# Precharge_2019_Test.net
KiCad netlist of a schematic drawn in EAGLE
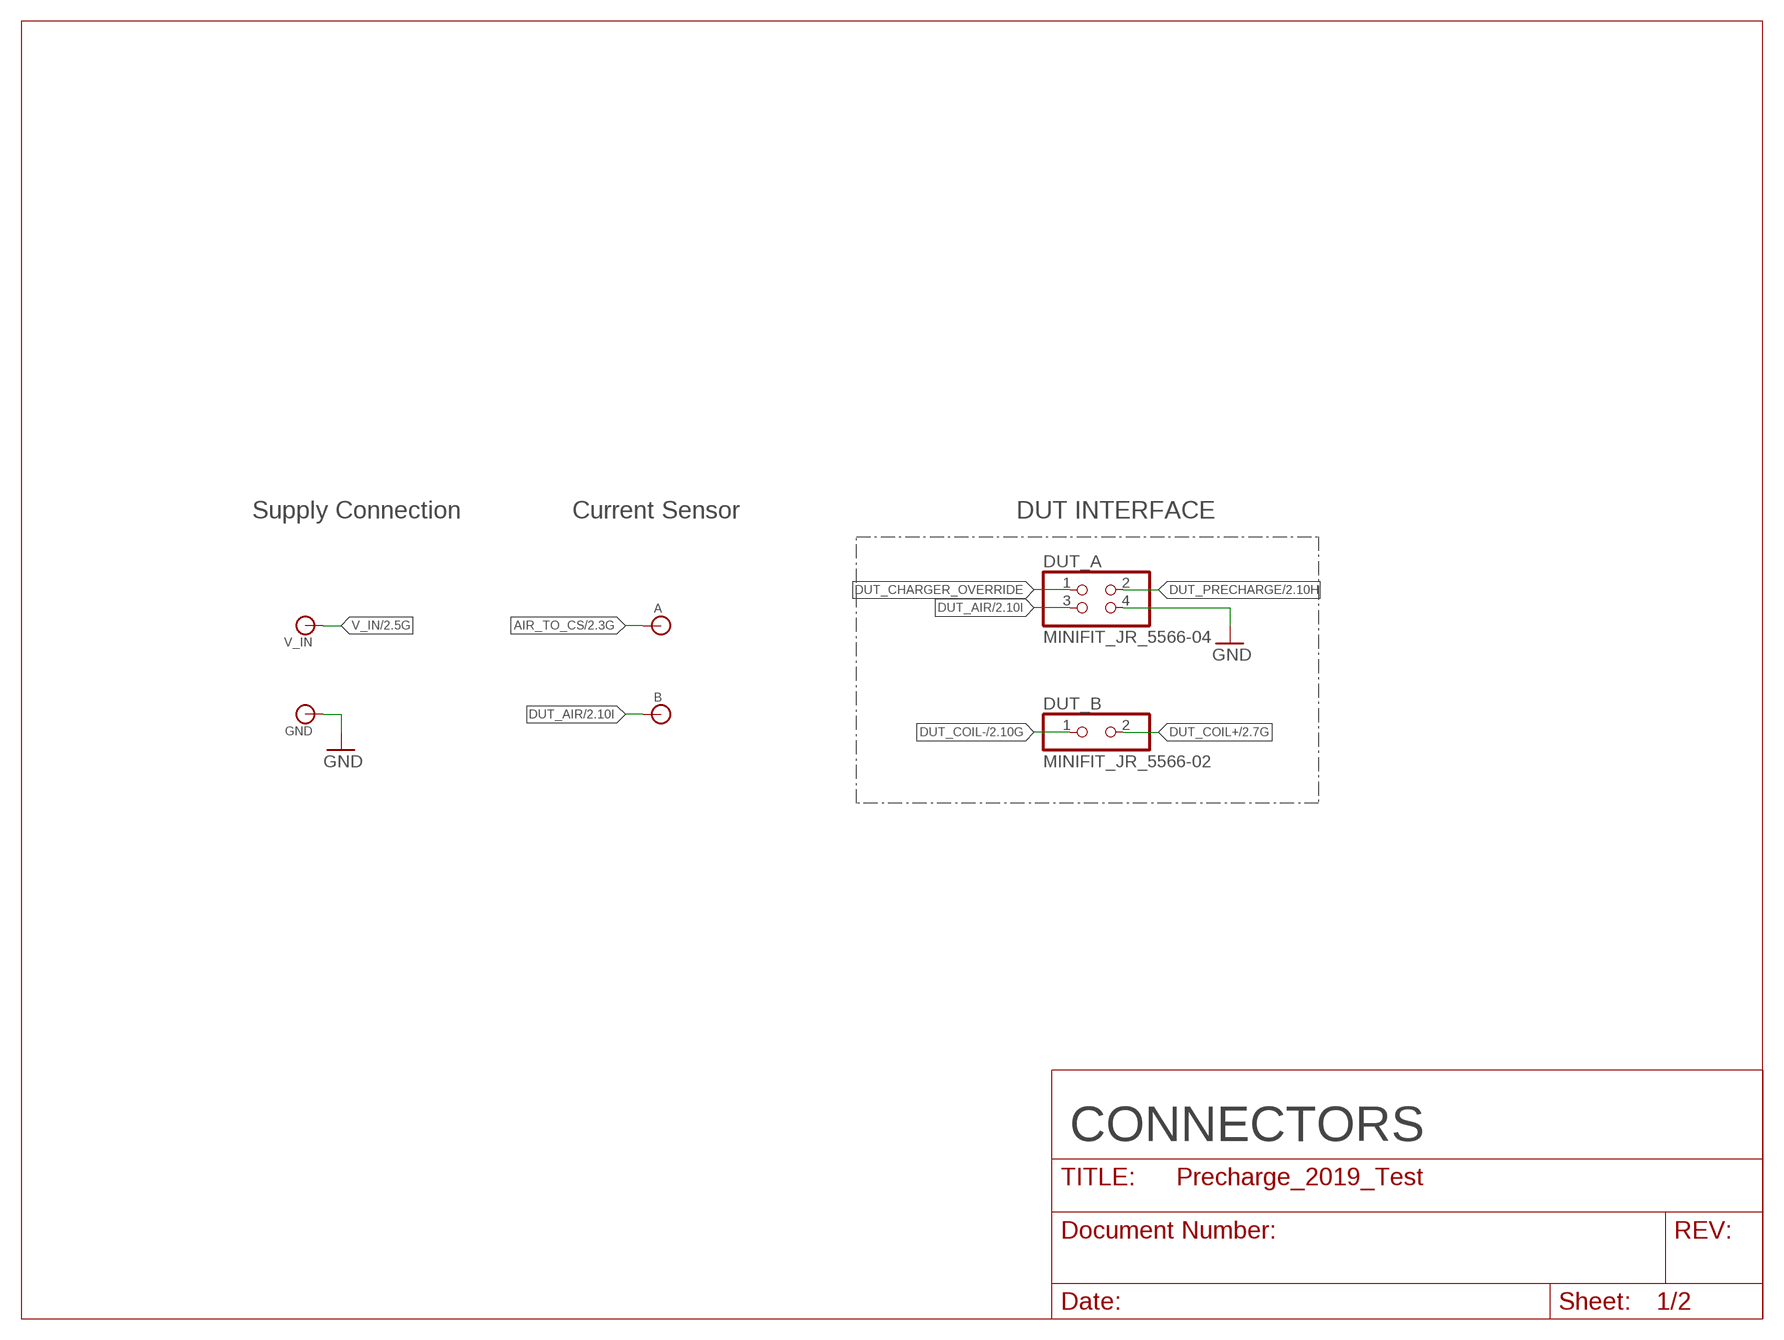
[diagram p0: schematic, sheet 1]
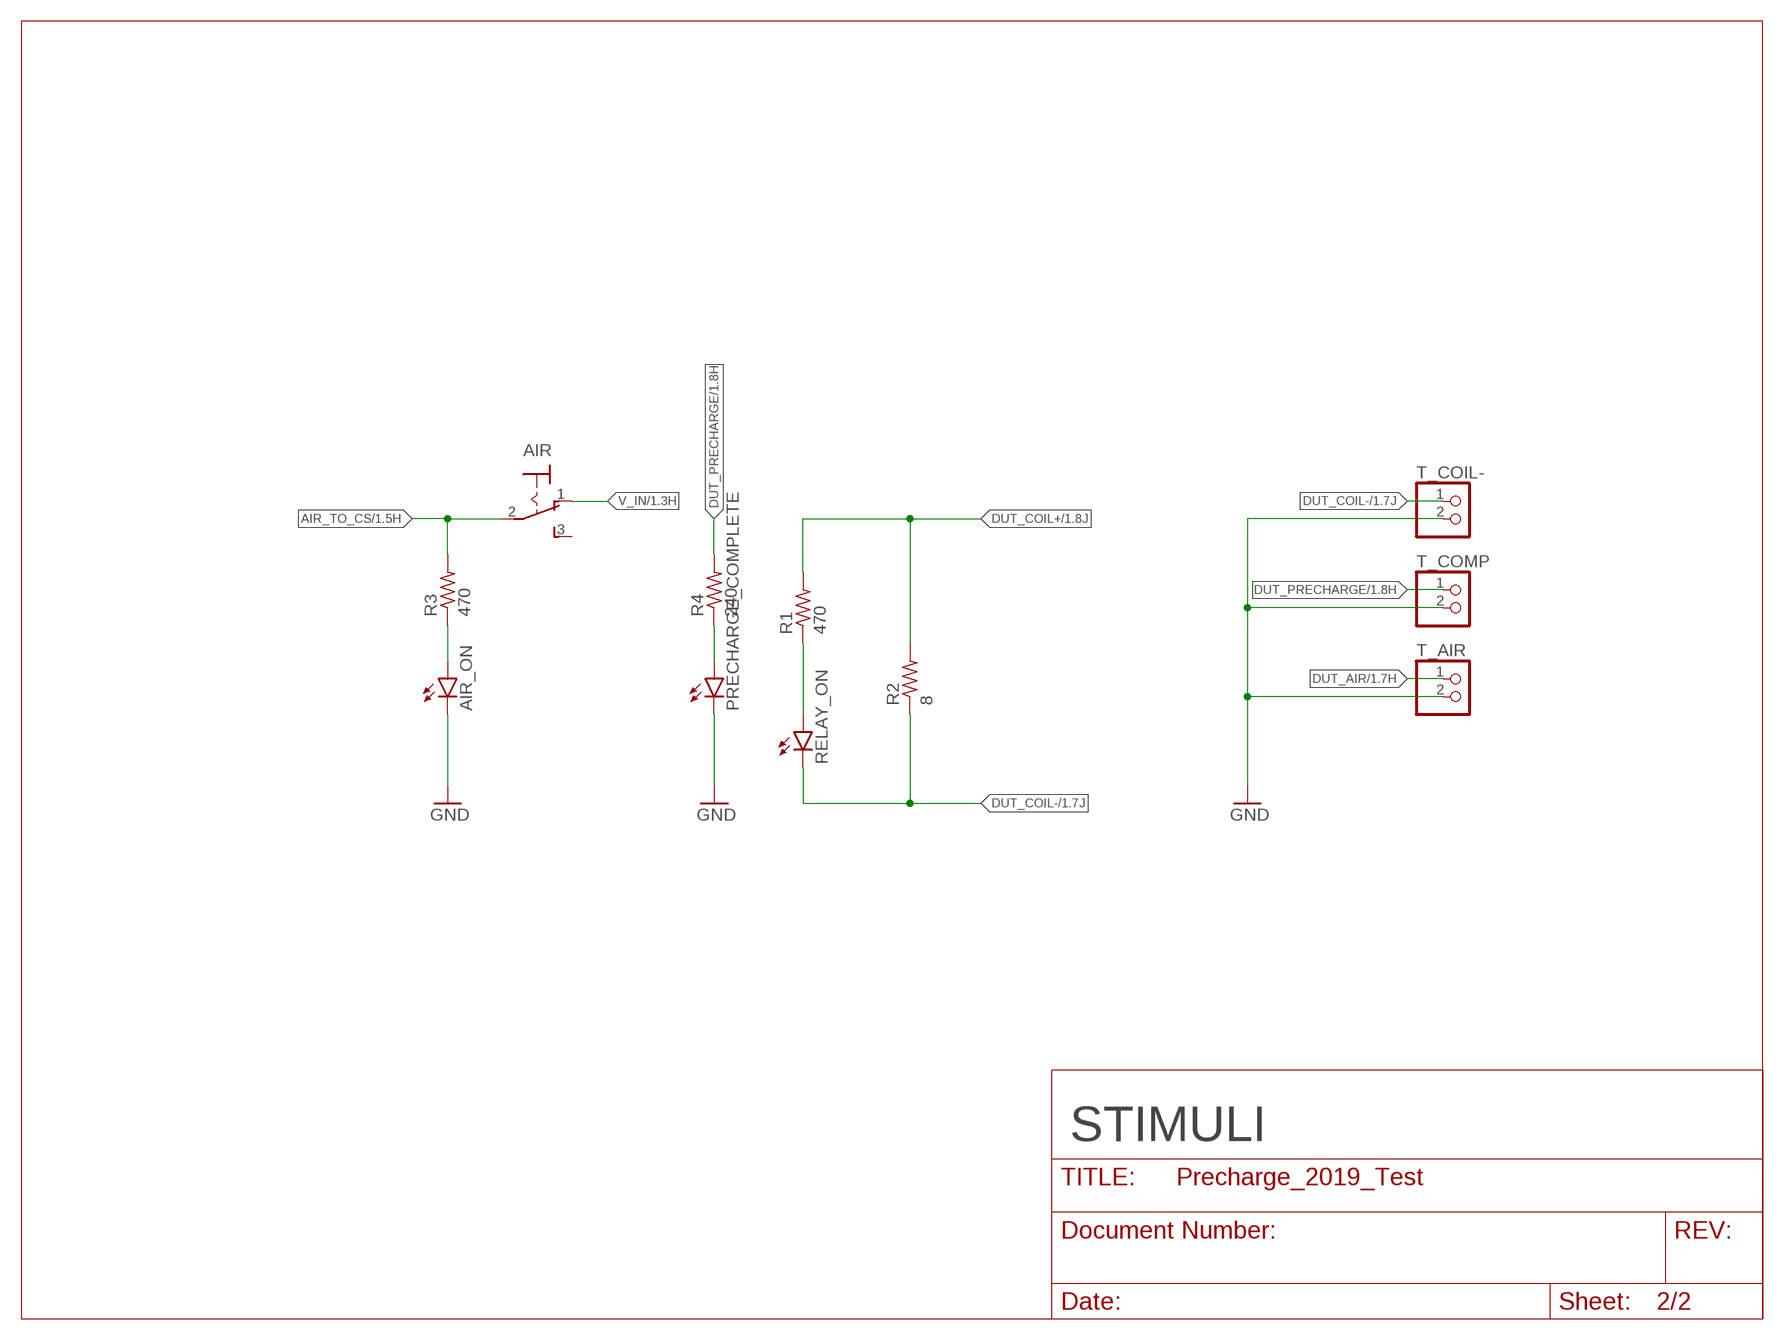
[diagram p1: schematic, sheet 2]

(export (version "E")
  (design (tool "Eeschema 10.0.6"))
  (components
    (comp (ref "AIR")
      (value "320-916")
      (footprint "eagle-import:320-916")
      (libsource (lib "eagle-import") (part "320-916"))
    )
    (comp (ref "AIR_ON")
      (value "LED0603")
      (footprint "eagle-import:LED-0603")
      (libsource (lib "eagle-import") (part "LED0603"))
    )
    (comp (ref "PRECHARGE_COMPLETE")
      (value "LED0603")
      (footprint "eagle-import:LED-0603")
      (libsource (lib "eagle-import") (part "LED0603"))
    )
    (comp (ref "R1")
      (value "470")
      (footprint "eagle-import:R0603")
      (libsource (lib "eagle-import") (part "R-US_R0603"))
    )
    (comp (ref "R2")
      (value "8")
      (footprint "eagle-import:R0603")
      (libsource (lib "eagle-import") (part "R-US_R0603"))
    )
    (comp (ref "R3")
      (value "470")
      (footprint "eagle-import:R0603")
      (libsource (lib "eagle-import") (part "R-US_R0603"))
    )
    (comp (ref "R4")
      (value "240")
      (footprint "eagle-import:R0603")
      (libsource (lib "eagle-import") (part "R-US_R0603"))
    )
    (comp (ref "RELAY_ON")
      (value "LED0603")
      (footprint "eagle-import:LED-0603")
      (libsource (lib "eagle-import") (part "LED0603"))
    )
    (comp (ref "T_AIR")
      (value "PINHD-1X2")
      (footprint "eagle-import:1X02")
      (libsource (lib "eagle-import") (part "PINHD-1X2"))
    )
    (comp (ref "T_COIL-")
      (value "PINHD-1X2")
      (footprint "eagle-import:1X02")
      (libsource (lib "eagle-import") (part "PINHD-1X2"))
    )
    (comp (ref "T_COMP")
      (value "PINHD-1X2")
      (footprint "eagle-import:1X02")
      (libsource (lib "eagle-import") (part "PINHD-1X2"))
    )
    (comp (ref "A")
      (value "BANANA_CONN")
      (footprint "eagle-import:BANANA_CONN")
      (libsource (lib "eagle-import") (part "BANANA_CONN"))
    )
    (comp (ref "B")
      (value "BANANA_CONN")
      (footprint "eagle-import:BANANA_CONN")
      (libsource (lib "eagle-import") (part "BANANA_CONN"))
    )
    (comp (ref "DUT_A")
      (value "MINIFIT_JR_5566-04")
      (footprint "eagle-import:MINIFIT_JR_5566-04")
      (libsource (lib "eagle-import") (part "MINIFIT_JR_5566-04"))
    )
    (comp (ref "DUT_B")
      (value "MINIFIT_JR_5566-02")
      (footprint "eagle-import:MINIFIT_JR_5566-02")
      (libsource (lib "eagle-import") (part "MINIFIT_JR_5566-02"))
    )
    (comp (ref "GND")
      (value "BANANA_CONN")
      (footprint "eagle-import:BANANA_CONN")
      (libsource (lib "eagle-import") (part "BANANA_CONN"))
    )
    (comp (ref "V_IN")
      (value "BANANA_CONN")
      (footprint "eagle-import:BANANA_CONN")
      (libsource (lib "eagle-import") (part "BANANA_CONN"))
    )
  )
  (nets
    (net (code "1") (name "AIR_TO_CS") (class "Default")
      (node (ref "A") (pin "P$1") (pinfunction "1_P$1") (pintype "passive"))
      (node (ref "AIR") (pin "2") (pinfunction "P_2") (pintype "passive"))
      (node (ref "R3") (pin "2") (pinfunction "2_2") (pintype "passive"))
    )
    (net (code "2") (name "DUT_AIR") (class "Default")
      (node (ref "B") (pin "P$1") (pinfunction "1_P$1") (pintype "passive"))
      (node (ref "DUT_A") (pin "3") (pinfunction "3_3") (pintype "passive"))
      (node (ref "T_AIR") (pin "1") (pinfunction "1_1") (pintype "passive"))
    )
    (net (code "3") (name "DUT_CHARGER_OVERRIDE") (class "Default")
      (node (ref "DUT_A") (pin "1") (pinfunction "1_1") (pintype "passive"))
    )
    (net (code "4") (name "DUT_COIL+") (class "Default")
      (node (ref "DUT_B") (pin "2") (pinfunction "2_2") (pintype "passive"))
      (node (ref "R1") (pin "2") (pinfunction "2_2") (pintype "passive"))
      (node (ref "R2") (pin "2") (pinfunction "2_2") (pintype "passive"))
    )
    (net (code "5") (name "DUT_COIL-") (class "Default")
      (node (ref "DUT_B") (pin "1") (pinfunction "1_1") (pintype "passive"))
      (node (ref "R2") (pin "1") (pinfunction "1_1") (pintype "passive"))
      (node (ref "RELAY_ON") (pin "C") (pinfunction "C_C") (pintype "passive"))
      (node (ref "T_COIL-") (pin "1") (pinfunction "1_1") (pintype "passive"))
    )
    (net (code "6") (name "DUT_PRECHARGE") (class "Default")
      (node (ref "DUT_A") (pin "2") (pinfunction "2_2") (pintype "passive"))
      (node (ref "R4") (pin "2") (pinfunction "2_2") (pintype "passive"))
      (node (ref "T_COMP") (pin "1") (pinfunction "1_1") (pintype "passive"))
    )
    (net (code "7") (name "GND") (class "Default")
      (node (ref "AIR_ON") (pin "C") (pinfunction "C_C") (pintype "passive"))
      (node (ref "DUT_A") (pin "4") (pinfunction "4_4") (pintype "passive"))
      (node (ref "GND") (pin "P$1") (pinfunction "1_P$1") (pintype "passive"))
      (node (ref "PRECHARGE_COMPLETE") (pin "C") (pinfunction "C_C") (pintype "passive"))
      (node (ref "T_AIR") (pin "2") (pinfunction "2_2") (pintype "passive"))
      (node (ref "T_COIL-") (pin "2") (pinfunction "2_2") (pintype "passive"))
      (node (ref "T_COMP") (pin "2") (pinfunction "2_2") (pintype "passive"))
    )
    (net (code "8") (name "Net-(AIR_ON-PadA)") (class "Default")
      (node (ref "AIR_ON") (pin "A") (pinfunction "A_A") (pintype "passive"))
      (node (ref "R3") (pin "1") (pinfunction "1_1") (pintype "passive"))
    )
    (net (code "9") (name "Net-(PRECHARGE_COMPLETE-PadA)") (class "Default")
      (node (ref "PRECHARGE_COMPLETE") (pin "A") (pinfunction "A_A") (pintype "passive"))
      (node (ref "R4") (pin "1") (pinfunction "1_1") (pintype "passive"))
    )
    (net (code "10") (name "Net-(R1-Pad1)") (class "Default")
      (node (ref "R1") (pin "1") (pinfunction "1_1") (pintype "passive"))
      (node (ref "RELAY_ON") (pin "A") (pinfunction "A_A") (pintype "passive"))
    )
    (net (code "11") (name "V_IN") (class "Default")
      (node (ref "AIR") (pin "1") (pinfunction "O_1") (pintype "passive"))
      (node (ref "V_IN") (pin "P$1") (pinfunction "1_P$1") (pintype "passive"))
    )
    (net (code "12") (name "unconnected-(AIR-S-Pad3)") (class "Default")
      (node (ref "AIR") (pin "3") (pinfunction "S_3") (pintype "passive"))
    )
  )
)
